# Qwiic_OLED_Breakout_NO_T.net
KiCad netlist of a schematic drawn in EAGLE
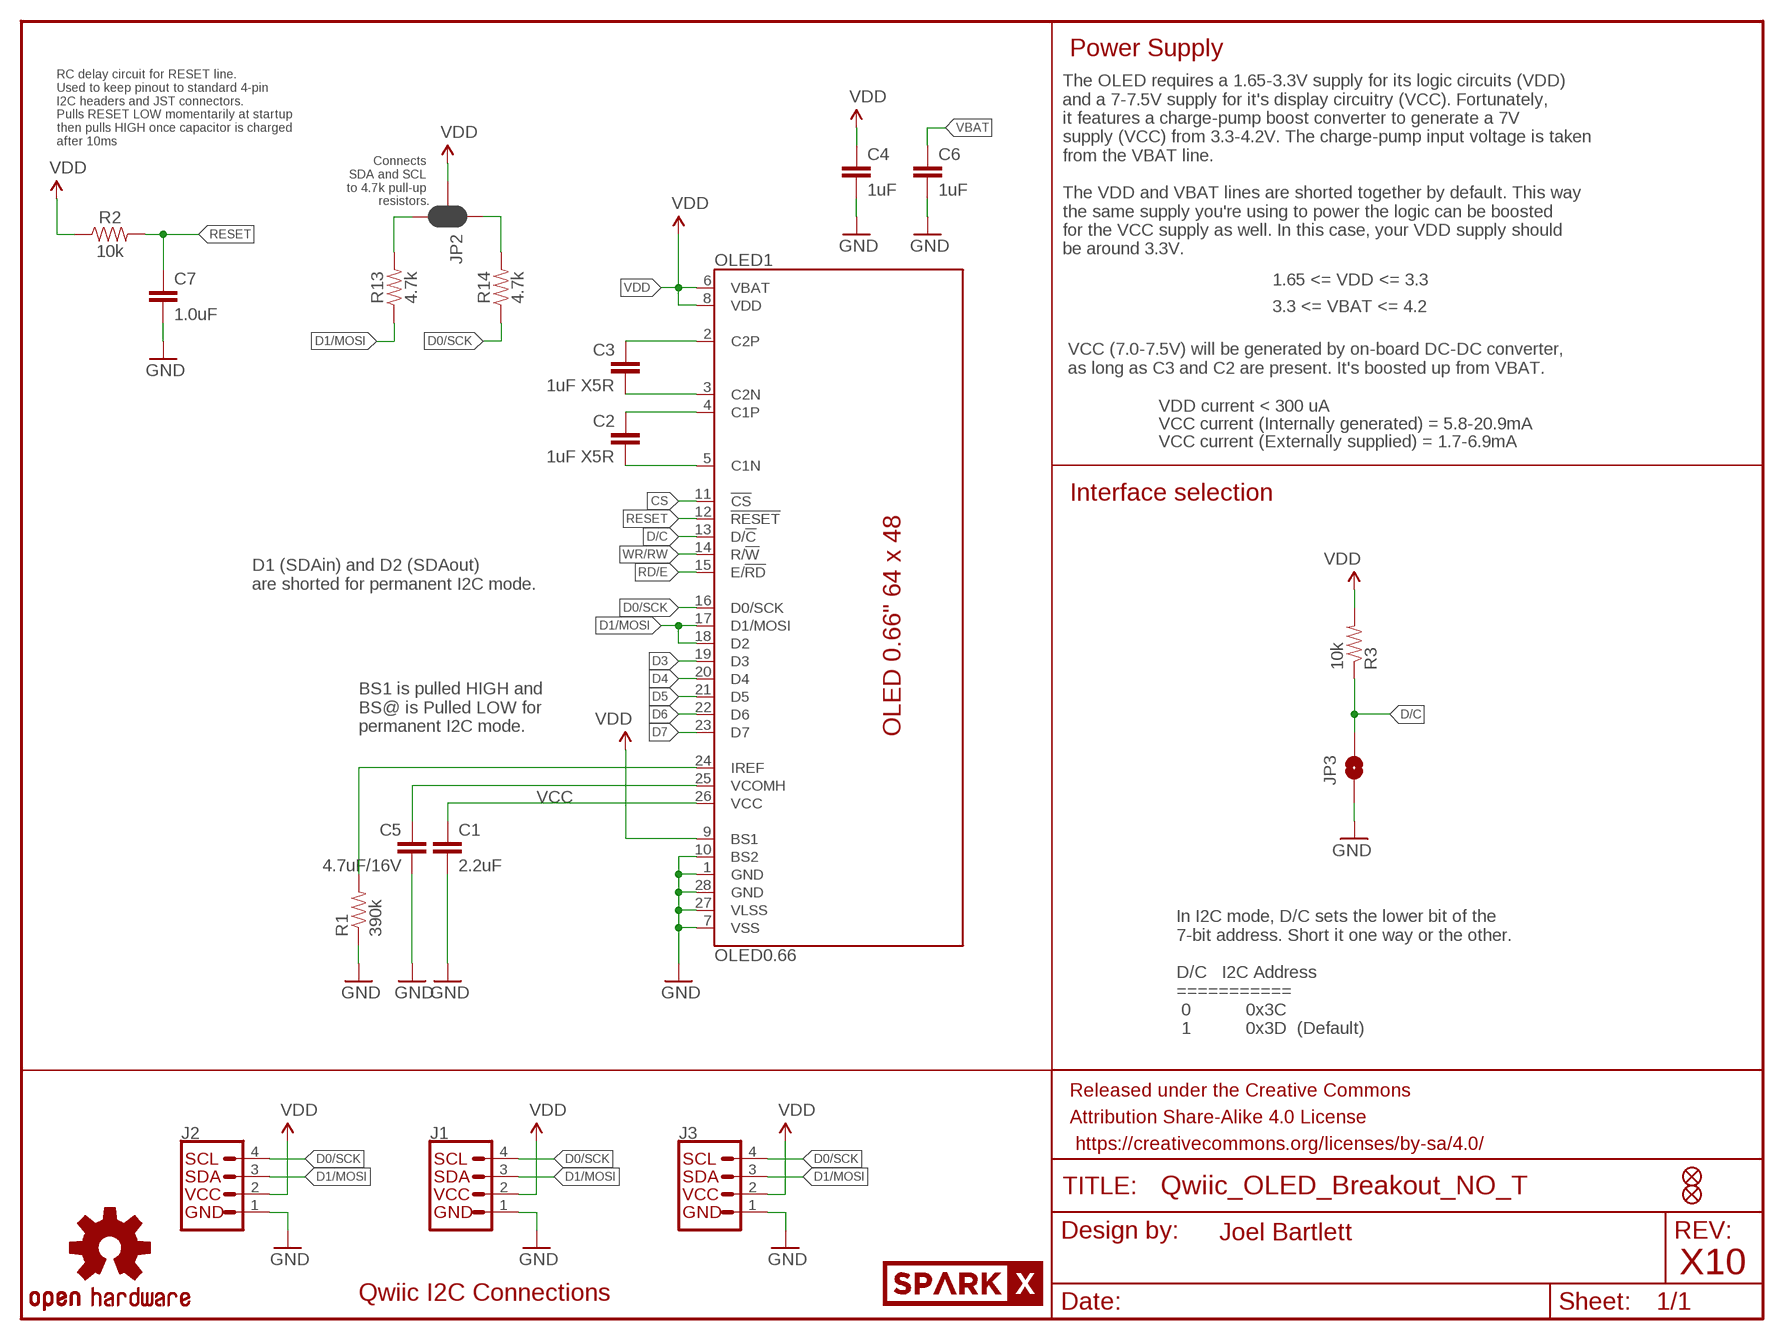
[diagram p0: schematic, sheet 1]

(export (version "E")
  (design (tool "Eeschema 10.0.6"))
  (components
    (comp (ref "C1")
      (value "2.2uF")
      (footprint "eagle-import:0805")
      (libsource (lib "eagle-import") (part "CAP0805"))
    )
    (comp (ref "C2")
      (value "1uF X5R")
      (footprint "eagle-import:0805")
      (libsource (lib "eagle-import") (part "CAP0805"))
    )
    (comp (ref "C3")
      (value "1uF X5R")
      (footprint "eagle-import:0805")
      (libsource (lib "eagle-import") (part "CAP0805"))
    )
    (comp (ref "C4")
      (value "1uF")
      (footprint "eagle-import:0603-CAP")
      (libsource (lib "eagle-import") (part "CAP0603-CAP"))
    )
    (comp (ref "C5")
      (value "4.7uF/16V")
      (footprint "eagle-import:1206")
      (libsource (lib "eagle-import") (part "CAP1206"))
    )
    (comp (ref "C6")
      (value "1uF")
      (footprint "eagle-import:0603-CAP")
      (libsource (lib "eagle-import") (part "CAP0603-CAP"))
    )
    (comp (ref "C7")
      (value "1.0uF")
      (footprint "eagle-import:0603")
      (libsource (lib "eagle-import") (part "1.0UF-0603-16V-10%"))
    )
    (comp (ref "FID1")
      (value "FIDUCIAL1X2")
      (footprint "eagle-import:FIDUCIAL-1X2")
      (libsource (lib "eagle-import") (part "FIDUCIAL1X2"))
    )
    (comp (ref "FID2")
      (value "FIDUCIAL1X2")
      (footprint "eagle-import:FIDUCIAL-1X2")
      (libsource (lib "eagle-import") (part "FIDUCIAL1X2"))
    )
    (comp (ref "FRAME1")
      (value "FRAME-LETTER")
      (footprint "eagle-import:CREATIVE_COMMONS")
      (libsource (lib "eagle-import") (part "FRAME-LETTER"))
    )
    (comp (ref "J1")
      (value "I2C_STANDARDJS-1MM")
      (footprint "eagle-import:1X04_1MM_RA")
      (libsource (lib "eagle-import") (part "I2C_STANDARDJS-1MM"))
    )
    (comp (ref "J2")
      (value "I2C_STANDARDJS-1MM")
      (footprint "eagle-import:1X04_1MM_RA")
      (libsource (lib "eagle-import") (part "I2C_STANDARDJS-1MM"))
    )
    (comp (ref "J3")
      (value "I2C_STANDARD_NO_SILK")
      (footprint "eagle-import:1X04_NO_SILK")
      (libsource (lib "eagle-import") (part "I2C_STANDARD_NO_SILK"))
    )
    (comp (ref "JP2")
      (value "JUMPER-SMT_3_2-NC_PASTE_SILK")
      (footprint "eagle-import:SMT-JUMPER_3_2-NC_PASTE_SILK")
      (libsource (lib "eagle-import") (part "JUMPER-SMT_3_2-NC_PASTE_SILK"))
    )
    (comp (ref "JP3")
      (value "JUMPER-SMT_2_NO_SILK")
      (footprint "eagle-import:SMT-JUMPER_2_NO_SILK")
      (libsource (lib "eagle-import") (part "JUMPER-SMT_2_NO_SILK"))
    )
    (comp (ref "LOGO3")
      (value "OSHW-LOGOS")
      (footprint "eagle-import:OSHW-LOGO-S")
      (libsource (lib "eagle-import") (part "OSHW-LOGOS"))
    )
    (comp (ref "OLED1")
      (value "OLED0.66")
      (footprint "eagle-import:OLED-0.66-64X48")
      (libsource (lib "eagle-import") (part "OLED0.66"))
    )
    (comp (ref "R1")
      (value "390k")
      (footprint "eagle-import:0603-RES")
      (libsource (lib "eagle-import") (part "RESISTOR0603-RES"))
    )
    (comp (ref "R2")
      (value "10k")
      (footprint "eagle-import:0603")
      (libsource (lib "eagle-import") (part "10KOHM-0603-1/10W-1%"))
    )
    (comp (ref "R3")
      (value "10k")
      (footprint "eagle-import:0603-RES")
      (libsource (lib "eagle-import") (part "RESISTOR0603-RES"))
    )
    (comp (ref "R13")
      (value "4.7k")
      (footprint "eagle-import:0603")
      (libsource (lib "eagle-import") (part "4.7KOHM-0603-1/10W-1%"))
    )
    (comp (ref "R14")
      (value "4.7k")
      (footprint "eagle-import:0603")
      (libsource (lib "eagle-import") (part "4.7KOHM-0603-1/10W-1%"))
    )
    (comp (ref "U$3")
      (value "SPARKX-LOGO2")
      (footprint "eagle-import:SPARKX-TINY")
      (libsource (lib "eagle-import") (part "SPARKX-LOGO2"))
    )
  )
  (nets
    (net (code "1") (name "/VCC") (class "Default")
      (node (ref "C1") (pin "1") (pinfunction "1_1") (pintype "passive"))
      (node (ref "OLED1") (pin "26") (pinfunction "VCC_26") (pintype "bidirectional"))
    )
    (net (code "2") (name "CS") (class "Default")
      (node (ref "OLED1") (pin "11") (pinfunction "~{CS}_11") (pintype "bidirectional"))
    )
    (net (code "3") (name "D0{slash}SCK") (class "Default")
      (node (ref "J1") (pin "4") (pinfunction "SCL_4") (pintype "passive"))
      (node (ref "J2") (pin "4") (pinfunction "SCL_4") (pintype "passive"))
      (node (ref "J3") (pin "4") (pinfunction "SCL_4") (pintype "passive"))
      (node (ref "OLED1") (pin "16") (pinfunction "D0/SCK_16") (pintype "bidirectional"))
      (node (ref "R14") (pin "1") (pinfunction "1_1") (pintype "passive"))
    )
    (net (code "4") (name "D1{slash}MOSI") (class "Default")
      (node (ref "J1") (pin "3") (pinfunction "SDA_3") (pintype "passive"))
      (node (ref "J2") (pin "3") (pinfunction "SDA_3") (pintype "passive"))
      (node (ref "J3") (pin "3") (pinfunction "SDA_3") (pintype "passive"))
      (node (ref "OLED1") (pin "17") (pinfunction "D1/MOSI_17") (pintype "bidirectional"))
      (node (ref "OLED1") (pin "18") (pinfunction "D2_18") (pintype "bidirectional"))
      (node (ref "R13") (pin "1") (pinfunction "1_1") (pintype "passive"))
    )
    (net (code "5") (name "D3") (class "Default")
      (node (ref "OLED1") (pin "19") (pinfunction "D3_19") (pintype "bidirectional"))
    )
    (net (code "6") (name "D4") (class "Default")
      (node (ref "OLED1") (pin "20") (pinfunction "D4_20") (pintype "bidirectional"))
    )
    (net (code "7") (name "D5") (class "Default")
      (node (ref "OLED1") (pin "21") (pinfunction "D5_21") (pintype "bidirectional"))
    )
    (net (code "8") (name "D6") (class "Default")
      (node (ref "OLED1") (pin "22") (pinfunction "D6_22") (pintype "bidirectional"))
    )
    (net (code "9") (name "D7") (class "Default")
      (node (ref "OLED1") (pin "23") (pinfunction "D7_23") (pintype "bidirectional"))
    )
    (net (code "10") (name "D{slash}C") (class "Default")
      (node (ref "JP3") (pin "2") (pinfunction "2_2") (pintype "passive"))
      (node (ref "OLED1") (pin "13") (pinfunction "D/~{C}_13") (pintype "bidirectional"))
      (node (ref "R3") (pin "1") (pinfunction "1_1") (pintype "passive"))
    )
    (net (code "11") (name "GND") (class "Default")
      (node (ref "C1") (pin "2") (pinfunction "2_2") (pintype "passive"))
      (node (ref "C4") (pin "2") (pinfunction "2_2") (pintype "passive"))
      (node (ref "C5") (pin "2") (pinfunction "2_2") (pintype "passive"))
      (node (ref "C6") (pin "2") (pinfunction "2_2") (pintype "passive"))
      (node (ref "C7") (pin "2") (pinfunction "2_2") (pintype "passive"))
      (node (ref "J1") (pin "1") (pinfunction "GND_1") (pintype "power_in"))
      (node (ref "J2") (pin "1") (pinfunction "GND_1") (pintype "power_in"))
      (node (ref "J3") (pin "1") (pinfunction "GND_1") (pintype "power_in"))
      (node (ref "JP3") (pin "1") (pinfunction "1_1") (pintype "passive"))
      (node (ref "OLED1") (pin "1") (pinfunction "GND_1") (pintype "bidirectional"))
      (node (ref "OLED1") (pin "10") (pinfunction "BS2_10") (pintype "bidirectional"))
      (node (ref "OLED1") (pin "27") (pinfunction "VLSS_27") (pintype "bidirectional"))
      (node (ref "OLED1") (pin "28") (pinfunction "GND_28") (pintype "bidirectional"))
      (node (ref "OLED1") (pin "7") (pinfunction "VSS_7") (pintype "bidirectional"))
      (node (ref "R1") (pin "1") (pinfunction "1_1") (pintype "passive"))
    )
    (net (code "12") (name "Net-(JP2-Pad1)") (class "Default")
      (node (ref "JP2") (pin "1") (pinfunction "1_1") (pintype "passive"))
      (node (ref "R14") (pin "2") (pinfunction "2_2") (pintype "passive"))
    )
    (net (code "13") (name "Net-(JP2-Pad3)") (class "Default")
      (node (ref "JP2") (pin "3") (pinfunction "3_3") (pintype "passive"))
      (node (ref "R13") (pin "2") (pinfunction "2_2") (pintype "passive"))
    )
    (net (code "14") (name "Net-(OLED1-C1N)") (class "Default")
      (node (ref "C2") (pin "2") (pinfunction "2_2") (pintype "passive"))
      (node (ref "OLED1") (pin "5") (pinfunction "C1N_5") (pintype "bidirectional"))
    )
    (net (code "15") (name "Net-(OLED1-C1P)") (class "Default")
      (node (ref "C2") (pin "1") (pinfunction "1_1") (pintype "passive"))
      (node (ref "OLED1") (pin "4") (pinfunction "C1P_4") (pintype "bidirectional"))
    )
    (net (code "16") (name "Net-(OLED1-C2N)") (class "Default")
      (node (ref "C3") (pin "2") (pinfunction "2_2") (pintype "passive"))
      (node (ref "OLED1") (pin "3") (pinfunction "C2N_3") (pintype "bidirectional"))
    )
    (net (code "17") (name "Net-(OLED1-C2P)") (class "Default")
      (node (ref "C3") (pin "1") (pinfunction "1_1") (pintype "passive"))
      (node (ref "OLED1") (pin "2") (pinfunction "C2P_2") (pintype "bidirectional"))
    )
    (net (code "18") (name "Net-(OLED1-IREF)") (class "Default")
      (node (ref "OLED1") (pin "24") (pinfunction "IREF_24") (pintype "bidirectional"))
      (node (ref "R1") (pin "2") (pinfunction "2_2") (pintype "passive"))
    )
    (net (code "19") (name "Net-(OLED1-VCOMH)") (class "Default")
      (node (ref "C5") (pin "1") (pinfunction "1_1") (pintype "passive"))
      (node (ref "OLED1") (pin "25") (pinfunction "VCOMH_25") (pintype "bidirectional"))
    )
    (net (code "20") (name "RD{slash}E") (class "Default")
      (node (ref "OLED1") (pin "15") (pinfunction "E/~{RD}_15") (pintype "bidirectional"))
    )
    (net (code "21") (name "RESET") (class "Default")
      (node (ref "C7") (pin "1") (pinfunction "1_1") (pintype "passive"))
      (node (ref "OLED1") (pin "12") (pinfunction "~{RESET}_12") (pintype "bidirectional"))
      (node (ref "R2") (pin "2") (pinfunction "2_2") (pintype "passive"))
    )
    (net (code "22") (name "VBAT") (class "Default")
      (node (ref "C6") (pin "1") (pinfunction "1_1") (pintype "passive"))
    )
    (net (code "23") (name "VDD") (class "Default")
      (node (ref "C4") (pin "1") (pinfunction "1_1") (pintype "passive"))
      (node (ref "J1") (pin "2") (pinfunction "VCC_2") (pintype "power_in"))
      (node (ref "J2") (pin "2") (pinfunction "VCC_2") (pintype "power_in"))
      (node (ref "J3") (pin "2") (pinfunction "VCC_2") (pintype "power_in"))
      (node (ref "JP2") (pin "2") (pinfunction "2_2") (pintype "passive"))
      (node (ref "OLED1") (pin "6") (pinfunction "VBAT_6") (pintype "bidirectional"))
      (node (ref "OLED1") (pin "8") (pinfunction "VDD_8") (pintype "bidirectional"))
      (node (ref "OLED1") (pin "9") (pinfunction "BS1_9") (pintype "bidirectional"))
      (node (ref "R2") (pin "1") (pinfunction "1_1") (pintype "passive"))
      (node (ref "R3") (pin "2") (pinfunction "2_2") (pintype "passive"))
    )
    (net (code "24") (name "WR{slash}RW") (class "Default")
      (node (ref "OLED1") (pin "14") (pinfunction "R/~{W}_14") (pintype "bidirectional"))
    )
  )
)
